# EIB_A79024-001.net
KiCad netlist of a schematic drawn in EAGLE
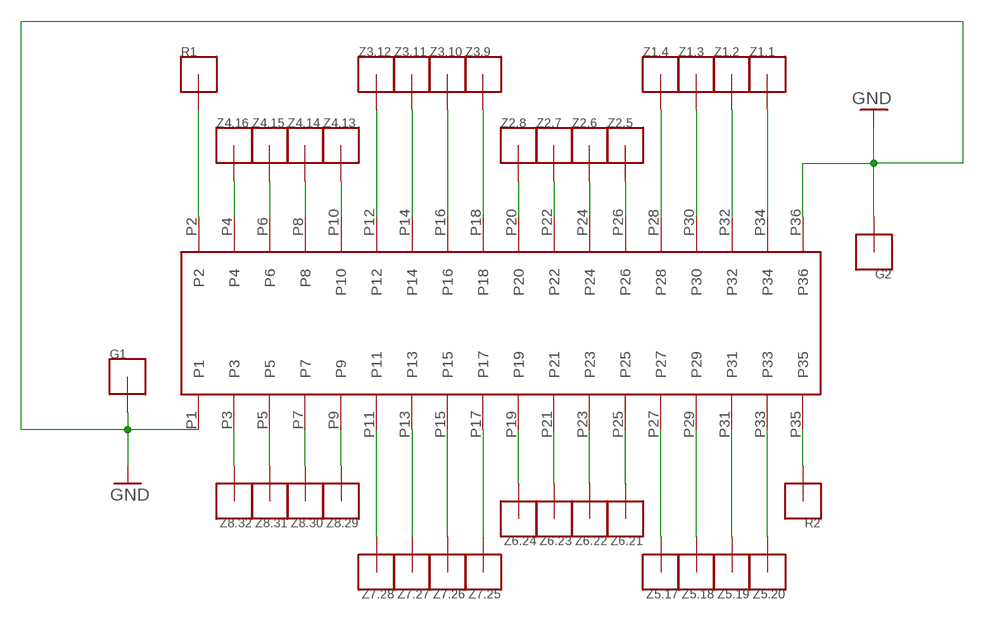
[diagram p0: schematic, sheet 1]

(export (version "E")
  (design (tool "Eeschema 10.0.6"))
  (components
    (comp (ref "A79024")
      (value "OMNETICS")
      (footprint "eagle-import:A79024")
      (libsource (lib "eagle-import") (part "OMNETICS"))
    )
    (comp (ref "G1")
      (value "S_P_HOLE")
      (footprint "eagle-import:S_P_HOLE")
      (libsource (lib "eagle-import") (part "S_P_HOLE"))
    )
    (comp (ref "G2")
      (value "S_P_HOLE")
      (footprint "eagle-import:S_P_HOLE")
      (libsource (lib "eagle-import") (part "S_P_HOLE"))
    )
    (comp (ref "R1")
      (value "S_P_HOLE")
      (footprint "eagle-import:S_P_HOLE")
      (libsource (lib "eagle-import") (part "S_P_HOLE"))
    )
    (comp (ref "R2")
      (value "S_P_HOLE")
      (footprint "eagle-import:S_P_HOLE")
      (libsource (lib "eagle-import") (part "S_P_HOLE"))
    )
    (comp (ref "Z1.1")
      (value "S_P_HOLE")
      (footprint "eagle-import:S_P_HOLE")
      (libsource (lib "eagle-import") (part "S_P_HOLE"))
    )
    (comp (ref "Z1.2")
      (value "S_P_HOLE")
      (footprint "eagle-import:S_P_HOLE")
      (libsource (lib "eagle-import") (part "S_P_HOLE"))
    )
    (comp (ref "Z1.3")
      (value "S_P_HOLE")
      (footprint "eagle-import:S_P_HOLE")
      (libsource (lib "eagle-import") (part "S_P_HOLE"))
    )
    (comp (ref "Z1.4")
      (value "S_P_HOLE")
      (footprint "eagle-import:S_P_HOLE")
      (libsource (lib "eagle-import") (part "S_P_HOLE"))
    )
    (comp (ref "Z2.5")
      (value "S_P_HOLE")
      (footprint "eagle-import:S_P_HOLE")
      (libsource (lib "eagle-import") (part "S_P_HOLE"))
    )
    (comp (ref "Z2.6")
      (value "S_P_HOLE")
      (footprint "eagle-import:S_P_HOLE")
      (libsource (lib "eagle-import") (part "S_P_HOLE"))
    )
    (comp (ref "Z2.7")
      (value "S_P_HOLE")
      (footprint "eagle-import:S_P_HOLE")
      (libsource (lib "eagle-import") (part "S_P_HOLE"))
    )
    (comp (ref "Z2.8")
      (value "S_P_HOLE")
      (footprint "eagle-import:S_P_HOLE")
      (libsource (lib "eagle-import") (part "S_P_HOLE"))
    )
    (comp (ref "Z3.9")
      (value "S_P_HOLE")
      (footprint "eagle-import:S_P_HOLE")
      (libsource (lib "eagle-import") (part "S_P_HOLE"))
    )
    (comp (ref "Z3.10")
      (value "S_P_HOLE")
      (footprint "eagle-import:S_P_HOLE")
      (libsource (lib "eagle-import") (part "S_P_HOLE"))
    )
    (comp (ref "Z3.11")
      (value "S_P_HOLE")
      (footprint "eagle-import:S_P_HOLE")
      (libsource (lib "eagle-import") (part "S_P_HOLE"))
    )
    (comp (ref "Z3.12")
      (value "S_P_HOLE")
      (footprint "eagle-import:S_P_HOLE")
      (libsource (lib "eagle-import") (part "S_P_HOLE"))
    )
    (comp (ref "Z4.13")
      (value "S_P_HOLE")
      (footprint "eagle-import:S_P_HOLE")
      (libsource (lib "eagle-import") (part "S_P_HOLE"))
    )
    (comp (ref "Z4.14")
      (value "S_P_HOLE")
      (footprint "eagle-import:S_P_HOLE")
      (libsource (lib "eagle-import") (part "S_P_HOLE"))
    )
    (comp (ref "Z4.15")
      (value "S_P_HOLE")
      (footprint "eagle-import:S_P_HOLE")
      (libsource (lib "eagle-import") (part "S_P_HOLE"))
    )
    (comp (ref "Z4.16")
      (value "S_P_HOLE")
      (footprint "eagle-import:S_P_HOLE")
      (libsource (lib "eagle-import") (part "S_P_HOLE"))
    )
    (comp (ref "Z5.17")
      (value "S_P_HOLE")
      (footprint "eagle-import:S_P_HOLE")
      (libsource (lib "eagle-import") (part "S_P_HOLE"))
    )
    (comp (ref "Z5.18")
      (value "S_P_HOLE")
      (footprint "eagle-import:S_P_HOLE")
      (libsource (lib "eagle-import") (part "S_P_HOLE"))
    )
    (comp (ref "Z5.19")
      (value "S_P_HOLE")
      (footprint "eagle-import:S_P_HOLE")
      (libsource (lib "eagle-import") (part "S_P_HOLE"))
    )
    (comp (ref "Z5.20")
      (value "S_P_HOLE")
      (footprint "eagle-import:S_P_HOLE")
      (libsource (lib "eagle-import") (part "S_P_HOLE"))
    )
    (comp (ref "Z6.21")
      (value "S_P_HOLE")
      (footprint "eagle-import:S_P_HOLE")
      (libsource (lib "eagle-import") (part "S_P_HOLE"))
    )
    (comp (ref "Z6.22")
      (value "S_P_HOLE")
      (footprint "eagle-import:S_P_HOLE")
      (libsource (lib "eagle-import") (part "S_P_HOLE"))
    )
    (comp (ref "Z6.23")
      (value "S_P_HOLE")
      (footprint "eagle-import:S_P_HOLE")
      (libsource (lib "eagle-import") (part "S_P_HOLE"))
    )
    (comp (ref "Z6.24")
      (value "S_P_HOLE")
      (footprint "eagle-import:S_P_HOLE")
      (libsource (lib "eagle-import") (part "S_P_HOLE"))
    )
    (comp (ref "Z7.25")
      (value "S_P_HOLE")
      (footprint "eagle-import:S_P_HOLE")
      (libsource (lib "eagle-import") (part "S_P_HOLE"))
    )
    (comp (ref "Z7.26")
      (value "S_P_HOLE")
      (footprint "eagle-import:S_P_HOLE")
      (libsource (lib "eagle-import") (part "S_P_HOLE"))
    )
    (comp (ref "Z7.27")
      (value "S_P_HOLE")
      (footprint "eagle-import:S_P_HOLE")
      (libsource (lib "eagle-import") (part "S_P_HOLE"))
    )
    (comp (ref "Z7.28")
      (value "S_P_HOLE")
      (footprint "eagle-import:S_P_HOLE")
      (libsource (lib "eagle-import") (part "S_P_HOLE"))
    )
    (comp (ref "Z8.29")
      (value "S_P_HOLE")
      (footprint "eagle-import:S_P_HOLE")
      (libsource (lib "eagle-import") (part "S_P_HOLE"))
    )
    (comp (ref "Z8.30")
      (value "S_P_HOLE")
      (footprint "eagle-import:S_P_HOLE")
      (libsource (lib "eagle-import") (part "S_P_HOLE"))
    )
    (comp (ref "Z8.31")
      (value "S_P_HOLE")
      (footprint "eagle-import:S_P_HOLE")
      (libsource (lib "eagle-import") (part "S_P_HOLE"))
    )
    (comp (ref "Z8.32")
      (value "S_P_HOLE")
      (footprint "eagle-import:S_P_HOLE")
      (libsource (lib "eagle-import") (part "S_P_HOLE"))
    )
  )
  (nets
    (net (code "1") (name "GND") (class "Default")
      (node (ref "A79024") (pin "P1") (pinfunction "P1_P1") (pintype "bidirectional"))
      (node (ref "A79024") (pin "P36") (pinfunction "P36_P36") (pintype "bidirectional"))
      (node (ref "G1") (pin "P1") (pinfunction "P1_P1") (pintype "bidirectional"))
      (node (ref "G2") (pin "P1") (pinfunction "P1_P1") (pintype "bidirectional"))
    )
    (net (code "2") (name "Net-(A79024-PadP2)") (class "Default")
      (node (ref "A79024") (pin "P2") (pinfunction "P2_P2") (pintype "bidirectional"))
      (node (ref "R1") (pin "P1") (pinfunction "P1_P1") (pintype "bidirectional"))
    )
    (net (code "3") (name "Net-(A79024-PadP3)") (class "Default")
      (node (ref "A79024") (pin "P3") (pinfunction "P3_P3") (pintype "bidirectional"))
      (node (ref "Z8.32") (pin "P1") (pinfunction "P1_P1") (pintype "bidirectional"))
    )
    (net (code "4") (name "Net-(A79024-PadP4)") (class "Default")
      (node (ref "A79024") (pin "P4") (pinfunction "P4_P4") (pintype "bidirectional"))
      (node (ref "Z4.16") (pin "P1") (pinfunction "P1_P1") (pintype "bidirectional"))
    )
    (net (code "5") (name "Net-(A79024-PadP5)") (class "Default")
      (node (ref "A79024") (pin "P5") (pinfunction "P5_P5") (pintype "bidirectional"))
      (node (ref "Z8.31") (pin "P1") (pinfunction "P1_P1") (pintype "bidirectional"))
    )
    (net (code "6") (name "Net-(A79024-PadP6)") (class "Default")
      (node (ref "A79024") (pin "P6") (pinfunction "P6_P6") (pintype "bidirectional"))
      (node (ref "Z4.15") (pin "P1") (pinfunction "P1_P1") (pintype "bidirectional"))
    )
    (net (code "7") (name "Net-(A79024-PadP7)") (class "Default")
      (node (ref "A79024") (pin "P7") (pinfunction "P7_P7") (pintype "bidirectional"))
      (node (ref "Z8.30") (pin "P1") (pinfunction "P1_P1") (pintype "bidirectional"))
    )
    (net (code "8") (name "Net-(A79024-PadP8)") (class "Default")
      (node (ref "A79024") (pin "P8") (pinfunction "P8_P8") (pintype "bidirectional"))
      (node (ref "Z4.14") (pin "P1") (pinfunction "P1_P1") (pintype "bidirectional"))
    )
    (net (code "9") (name "Net-(A79024-PadP9)") (class "Default")
      (node (ref "A79024") (pin "P9") (pinfunction "P9_P9") (pintype "bidirectional"))
      (node (ref "Z8.29") (pin "P1") (pinfunction "P1_P1") (pintype "bidirectional"))
    )
    (net (code "10") (name "Net-(A79024-PadP10)") (class "Default")
      (node (ref "A79024") (pin "P10") (pinfunction "P10_P10") (pintype "bidirectional"))
      (node (ref "Z4.13") (pin "P1") (pinfunction "P1_P1") (pintype "bidirectional"))
    )
    (net (code "11") (name "Net-(A79024-PadP11)") (class "Default")
      (node (ref "A79024") (pin "P11") (pinfunction "P11_P11") (pintype "bidirectional"))
      (node (ref "Z7.28") (pin "P1") (pinfunction "P1_P1") (pintype "bidirectional"))
    )
    (net (code "12") (name "Net-(A79024-PadP12)") (class "Default")
      (node (ref "A79024") (pin "P12") (pinfunction "P12_P12") (pintype "bidirectional"))
      (node (ref "Z3.12") (pin "P1") (pinfunction "P1_P1") (pintype "bidirectional"))
    )
    (net (code "13") (name "Net-(A79024-PadP13)") (class "Default")
      (node (ref "A79024") (pin "P13") (pinfunction "P13_P13") (pintype "bidirectional"))
      (node (ref "Z7.27") (pin "P1") (pinfunction "P1_P1") (pintype "bidirectional"))
    )
    (net (code "14") (name "Net-(A79024-PadP14)") (class "Default")
      (node (ref "A79024") (pin "P14") (pinfunction "P14_P14") (pintype "bidirectional"))
      (node (ref "Z3.11") (pin "P1") (pinfunction "P1_P1") (pintype "bidirectional"))
    )
    (net (code "15") (name "Net-(A79024-PadP15)") (class "Default")
      (node (ref "A79024") (pin "P15") (pinfunction "P15_P15") (pintype "bidirectional"))
      (node (ref "Z7.26") (pin "P1") (pinfunction "P1_P1") (pintype "bidirectional"))
    )
    (net (code "16") (name "Net-(A79024-PadP16)") (class "Default")
      (node (ref "A79024") (pin "P16") (pinfunction "P16_P16") (pintype "bidirectional"))
      (node (ref "Z3.10") (pin "P1") (pinfunction "P1_P1") (pintype "bidirectional"))
    )
    (net (code "17") (name "Net-(A79024-PadP17)") (class "Default")
      (node (ref "A79024") (pin "P17") (pinfunction "P17_P17") (pintype "bidirectional"))
      (node (ref "Z7.25") (pin "P1") (pinfunction "P1_P1") (pintype "bidirectional"))
    )
    (net (code "18") (name "Net-(A79024-PadP18)") (class "Default")
      (node (ref "A79024") (pin "P18") (pinfunction "P18_P18") (pintype "bidirectional"))
      (node (ref "Z3.9") (pin "P1") (pinfunction "P1_P1") (pintype "bidirectional"))
    )
    (net (code "19") (name "Net-(A79024-PadP19)") (class "Default")
      (node (ref "A79024") (pin "P19") (pinfunction "P19_P19") (pintype "bidirectional"))
      (node (ref "Z6.24") (pin "P1") (pinfunction "P1_P1") (pintype "bidirectional"))
    )
    (net (code "20") (name "Net-(A79024-PadP20)") (class "Default")
      (node (ref "A79024") (pin "P20") (pinfunction "P20_P20") (pintype "bidirectional"))
      (node (ref "Z2.8") (pin "P1") (pinfunction "P1_P1") (pintype "bidirectional"))
    )
    (net (code "21") (name "Net-(A79024-PadP21)") (class "Default")
      (node (ref "A79024") (pin "P21") (pinfunction "P21_P21") (pintype "bidirectional"))
      (node (ref "Z6.23") (pin "P1") (pinfunction "P1_P1") (pintype "bidirectional"))
    )
    (net (code "22") (name "Net-(A79024-PadP22)") (class "Default")
      (node (ref "A79024") (pin "P22") (pinfunction "P22_P22") (pintype "bidirectional"))
      (node (ref "Z2.7") (pin "P1") (pinfunction "P1_P1") (pintype "bidirectional"))
    )
    (net (code "23") (name "Net-(A79024-PadP23)") (class "Default")
      (node (ref "A79024") (pin "P23") (pinfunction "P23_P23") (pintype "bidirectional"))
      (node (ref "Z6.22") (pin "P1") (pinfunction "P1_P1") (pintype "bidirectional"))
    )
    (net (code "24") (name "Net-(A79024-PadP24)") (class "Default")
      (node (ref "A79024") (pin "P24") (pinfunction "P24_P24") (pintype "bidirectional"))
      (node (ref "Z2.6") (pin "P1") (pinfunction "P1_P1") (pintype "bidirectional"))
    )
    (net (code "25") (name "Net-(A79024-PadP25)") (class "Default")
      (node (ref "A79024") (pin "P25") (pinfunction "P25_P25") (pintype "bidirectional"))
      (node (ref "Z6.21") (pin "P1") (pinfunction "P1_P1") (pintype "bidirectional"))
    )
    (net (code "26") (name "Net-(A79024-PadP26)") (class "Default")
      (node (ref "A79024") (pin "P26") (pinfunction "P26_P26") (pintype "bidirectional"))
      (node (ref "Z2.5") (pin "P1") (pinfunction "P1_P1") (pintype "bidirectional"))
    )
    (net (code "27") (name "Net-(A79024-PadP27)") (class "Default")
      (node (ref "A79024") (pin "P27") (pinfunction "P27_P27") (pintype "bidirectional"))
      (node (ref "Z5.17") (pin "P1") (pinfunction "P1_P1") (pintype "bidirectional"))
    )
    (net (code "28") (name "Net-(A79024-PadP28)") (class "Default")
      (node (ref "A79024") (pin "P28") (pinfunction "P28_P28") (pintype "bidirectional"))
      (node (ref "Z1.4") (pin "P1") (pinfunction "P1_P1") (pintype "bidirectional"))
    )
    (net (code "29") (name "Net-(A79024-PadP29)") (class "Default")
      (node (ref "A79024") (pin "P29") (pinfunction "P29_P29") (pintype "bidirectional"))
      (node (ref "Z5.18") (pin "P1") (pinfunction "P1_P1") (pintype "bidirectional"))
    )
    (net (code "30") (name "Net-(A79024-PadP30)") (class "Default")
      (node (ref "A79024") (pin "P30") (pinfunction "P30_P30") (pintype "bidirectional"))
      (node (ref "Z1.3") (pin "P1") (pinfunction "P1_P1") (pintype "bidirectional"))
    )
    (net (code "31") (name "Net-(A79024-PadP31)") (class "Default")
      (node (ref "A79024") (pin "P31") (pinfunction "P31_P31") (pintype "bidirectional"))
      (node (ref "Z5.19") (pin "P1") (pinfunction "P1_P1") (pintype "bidirectional"))
    )
    (net (code "32") (name "Net-(A79024-PadP32)") (class "Default")
      (node (ref "A79024") (pin "P32") (pinfunction "P32_P32") (pintype "bidirectional"))
      (node (ref "Z1.2") (pin "P1") (pinfunction "P1_P1") (pintype "bidirectional"))
    )
    (net (code "33") (name "Net-(A79024-PadP33)") (class "Default")
      (node (ref "A79024") (pin "P33") (pinfunction "P33_P33") (pintype "bidirectional"))
      (node (ref "Z5.20") (pin "P1") (pinfunction "P1_P1") (pintype "bidirectional"))
    )
    (net (code "34") (name "Net-(A79024-PadP34)") (class "Default")
      (node (ref "A79024") (pin "P34") (pinfunction "P34_P34") (pintype "bidirectional"))
      (node (ref "Z1.1") (pin "P1") (pinfunction "P1_P1") (pintype "bidirectional"))
    )
    (net (code "35") (name "Net-(A79024-PadP35)") (class "Default")
      (node (ref "A79024") (pin "P35") (pinfunction "P35_P35") (pintype "bidirectional"))
      (node (ref "R2") (pin "P1") (pinfunction "P1_P1") (pintype "bidirectional"))
    )
  )
)
